# Regulador.net
KiCad netlist of a schematic drawn in Altium Designer
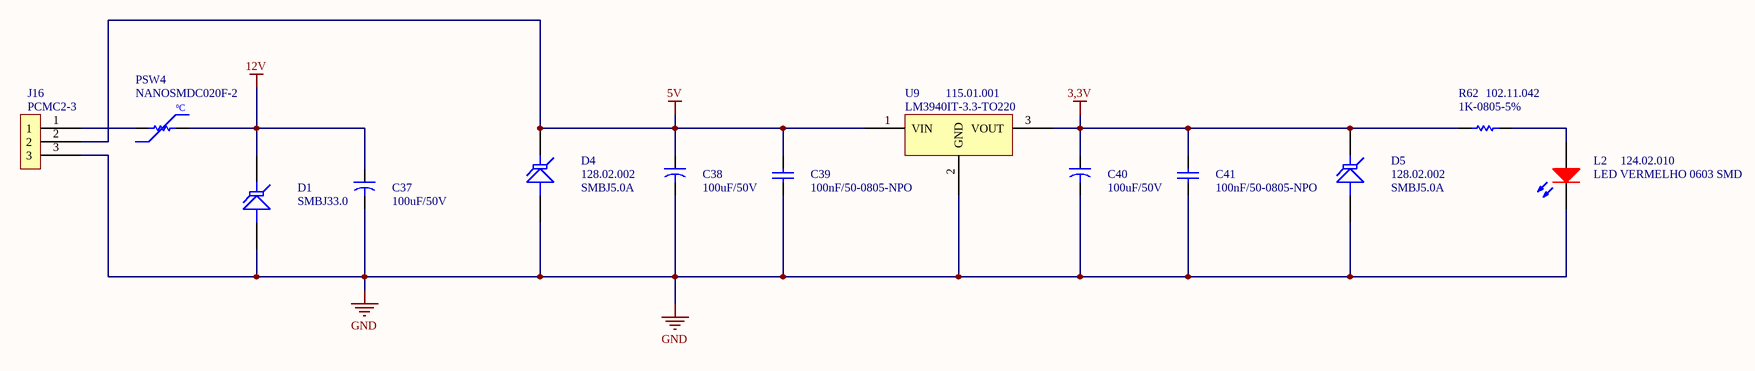
[diagram p0: Regulador.SchDoc]

(export (version "E")
  (design (tool "Eeschema 10.0.6"))
  (components
    (comp (ref "C37")
      (value "100uF/50V")
      (footprint "CAP POL 8x12mm")
      (libsource (lib "AquinoLib") (part "100uF/50V"))
    )
    (comp (ref "C38")
      (value "100uF/50V")
      (footprint "CAP POL 8x12mm")
      (libsource (lib "AquinoLib") (part "100uF/50V"))
    )
    (comp (ref "C39")
      (value "100nF/50-0805-NPO")
      (footprint "0805-REVISADO ONDA")
      (libsource (lib "AquinoLib") (part "100nF/50-0805-NPO"))
    )
    (comp (ref "C40")
      (value "100uF/50V")
      (footprint "CAP POL 8x12mm")
      (libsource (lib "AquinoLib") (part "100uF/50V"))
    )
    (comp (ref "C41")
      (value "100nF/50-0805-NPO")
      (footprint "0805-REVISADO ONDA")
      (libsource (lib "AquinoLib") (part "100nF/50-0805-NPO"))
    )
    (comp (ref "D1")
      (value "SMBJ33.0")
      (footprint "SMB/DO214AA-REVISADO ONDA")
      (description "SMBJ5.0A")
      (libsource (lib "AquinoLib") (part "SMBJ5.0A"))
    )
    (comp (ref "D4")
      (value "SMBJ5.0A")
      (footprint "SMB/DO214AA-REVISADO ONDA")
      (fields (field (name "ERP") "128.02.002"))
      (libsource (lib "AquinoLib") (part "SMBJ5.0A"))
    )
    (comp (ref "D5")
      (value "SMBJ5.0A")
      (footprint "SMB/DO214AA-REVISADO ONDA")
      (fields (field (name "ERP") "128.02.002"))
      (libsource (lib "AquinoLib") (part "SMBJ5.0A"))
    )
    (comp (ref "J16")
      (value "PCMC2-3")
      (footprint "CONECTOR HYLOCK 3 VIAS")
      (libsource (lib "AquinoLib") (part "PCMC2-3"))
    )
    (comp (ref "L2")
      (value "LED VERMELHO 0603 SMD")
      (footprint "LED 0805 - REVISADO ONDA")
      (fields (field (name "ERP") "124.02.010"))
      (libsource (lib "AquinoLib") (part "LED VERMELHO 0603 SMD"))
    )
    (comp (ref "PSW4")
      (value "NANOSMDC020F-2")
      (footprint "1206-REVISADO ONDA")
      (libsource (lib "AquinoLib") (part "POLYSWITCH 200mA"))
    )
    (comp (ref "R62")
      (value "1K-0805-5%")
      (footprint "0805-REVISADO ONDA")
      (fields (field (name "ERP") "102.11.042"))
      (libsource (lib "AquinoLib") (part "1K-0805-5%"))
    )
    (comp (ref "U9")
      (value "LM3940IT-3.3-TO220")
      (footprint "TO-263")
      (fields (field (name "ERP") "115.01.001"))
      (libsource (lib "ChaveDigital3") (part "LM3940IT-3.3-TO220"))
    )
  )
  (nets
    (net (code "1") (name "3,3V") (class "Default")
      (node (ref "C40") (pin "1") (pinfunction "1_1") (pintype "passive"))
      (node (ref "C41") (pin "2") (pinfunction "2_2") (pintype "passive"))
      (node (ref "D5") (pin "2") (pinfunction "K_2") (pintype "passive"))
      (node (ref "R62") (pin "1") (pinfunction "1_1") (pintype "passive"))
      (node (ref "U9") (pin "3") (pinfunction "VOUT_3") (pintype "passive"))
    )
    (net (code "2") (name "5V") (class "Default")
      (node (ref "C38") (pin "1") (pinfunction "1_1") (pintype "passive"))
      (node (ref "C39") (pin "2") (pinfunction "2_2") (pintype "passive"))
      (node (ref "D4") (pin "2") (pinfunction "K_2") (pintype "passive"))
      (node (ref "J16") (pin "2") (pinfunction "2_2") (pintype "passive"))
      (node (ref "U9") (pin "1") (pinfunction "VIN_1") (pintype "passive"))
    )
    (net (code "3") (name "12V") (class "Default")
      (node (ref "C37") (pin "1") (pinfunction "1_1") (pintype "passive"))
      (node (ref "D1") (pin "2") (pinfunction "K_2") (pintype "passive"))
      (node (ref "PSW4") (pin "2") (pinfunction "2_2") (pintype "passive"))
    )
    (net (code "4") (name "GND") (class "Default")
      (node (ref "C37") (pin "2") (pinfunction "2_2") (pintype "passive"))
      (node (ref "C38") (pin "2") (pinfunction "2_2") (pintype "passive"))
      (node (ref "C39") (pin "1") (pinfunction "1_1") (pintype "passive"))
      (node (ref "C40") (pin "2") (pinfunction "2_2") (pintype "passive"))
      (node (ref "C41") (pin "1") (pinfunction "1_1") (pintype "passive"))
      (node (ref "D1") (pin "1") (pinfunction "A_1") (pintype "passive"))
      (node (ref "D4") (pin "1") (pinfunction "A_1") (pintype "passive"))
      (node (ref "D5") (pin "1") (pinfunction "A_1") (pintype "passive"))
      (node (ref "J16") (pin "3") (pinfunction "3_3") (pintype "passive"))
      (node (ref "L2") (pin "2") (pinfunction "K_2") (pintype "passive"))
      (node (ref "U9") (pin "2") (pinfunction "GND_2") (pintype "passive"))
    )
    (net (code "5") (name "Net-(J16-Pad1)") (class "Default")
      (node (ref "J16") (pin "1") (pinfunction "1_1") (pintype "passive"))
      (node (ref "PSW4") (pin "1") (pinfunction "1_1") (pintype "passive"))
    )
    (net (code "6") (name "Net-(L2-A)") (class "Default")
      (node (ref "L2") (pin "1") (pinfunction "A_1") (pintype "passive"))
      (node (ref "R62") (pin "2") (pinfunction "2_2") (pintype "passive"))
    )
  )
)
